# communication.net
KiCad netlist of a schematic drawn in Altium Designer
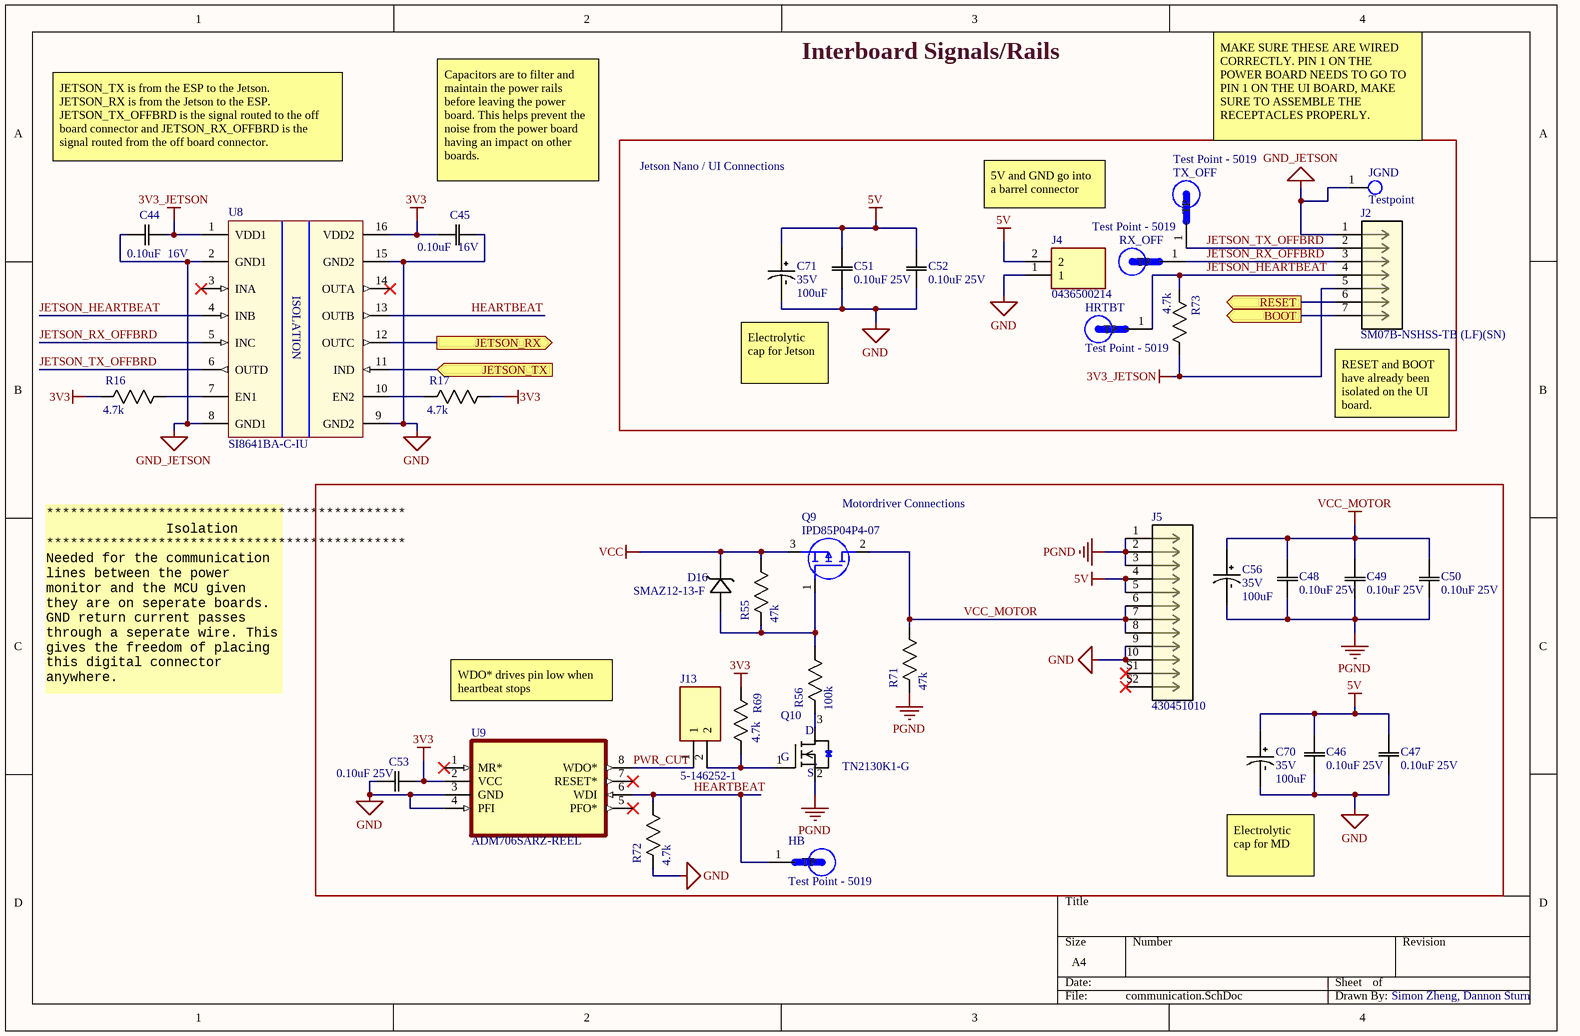
[diagram p0: communication.SchDoc]

(export (version "E")
  (design (tool "Eeschema 10.0.6"))
  (components
    (comp (ref "C44")
      (value "0.10uF")
      (footprint "0603")
      (description "CAP CER 0.10UF 16V X5R 0603")
      (fields
        (field (name "TOLERANCE") "10%")
        (field (name "RATING") "16V")
        (field (name "PART NUMBER") "CAP 0.10uF 16V")
      )
      (libsource (lib "capacitor_library") (part "CAP 0.10uF 16V"))
    )
    (comp (ref "C45")
      (value "0.10uF")
      (footprint "0603")
      (description "CAP CER 0.10UF 16V X5R 0603")
      (fields
        (field (name "TOLERANCE") "10%")
        (field (name "RATING") "16V")
        (field (name "PART NUMBER") "CAP 0.10uF 16V")
      )
      (libsource (lib "capacitor_library") (part "CAP 0.10uF 16V"))
    )
    (comp (ref "C46")
      (value "0.10uF 25V")
      (footprint "0603")
      (description "CAP CER 0.10UF 25V X7R 0603")
      (fields (field (name "TOLERANCE") "10%") (field (name "PART NUMBER") "CAP 0.10uF 25V"))
      (libsource (lib "capacitor_library") (part "CAP 0.10uF 25V"))
    )
    (comp (ref "C47")
      (value "0.10uF 25V")
      (footprint "0603")
      (description "CAP CER 0.10UF 25V X7R 0603")
      (fields (field (name "TOLERANCE") "10%") (field (name "PART NUMBER") "CAP 0.10uF 25V"))
      (libsource (lib "capacitor_library") (part "CAP 0.10uF 25V"))
    )
    (comp (ref "C48")
      (value "0.10uF 25V")
      (footprint "0805")
      (description "CAP CER 0.10UF 25V X7R 0805")
      (fields (field (name "TOLERANCE") "10%") (field (name "PART NUMBER") "CAP 0.10uF 25V"))
      (libsource (lib "capacitor_library") (part "CAP 0.10uF 25V"))
    )
    (comp (ref "C49")
      (value "0.10uF 25V")
      (footprint "0603")
      (description "CAP CER 0.10UF 25V X7R 0603")
      (fields (field (name "TOLERANCE") "10%") (field (name "PART NUMBER") "CAP 0.10uF 25V"))
      (libsource (lib "capacitor_library") (part "CAP 0.10uF 25V"))
    )
    (comp (ref "C50")
      (value "0.10uF 25V")
      (footprint "0603")
      (description "CAP CER 0.10UF 25V X7R 0603")
      (fields (field (name "TOLERANCE") "10%") (field (name "PART NUMBER") "CAP 0.10uF 25V"))
      (libsource (lib "capacitor_library") (part "CAP 0.10uF 25V"))
    )
    (comp (ref "C51")
      (value "0.10uF 25V")
      (footprint "0603")
      (description "CAP CER 0.10UF 25V X7R 0603")
      (fields (field (name "TOLERANCE") "10%") (field (name "PART NUMBER") "CAP 0.10uF 25V"))
      (libsource (lib "capacitor_library") (part "CAP 0.10uF 25V"))
    )
    (comp (ref "C52")
      (value "0.10uF 25V")
      (footprint "0603")
      (description "CAP CER 0.10UF 25V X7R 0603")
      (fields (field (name "TOLERANCE") "10%") (field (name "PART NUMBER") "CAP 0.10uF 25V"))
      (libsource (lib "capacitor_library") (part "CAP 0.10uF 25V"))
    )
    (comp (ref "C53")
      (value "0.10uF 25V")
      (footprint "0603")
      (description "CAP CER 0.10UF 25V X7R 0603")
      (fields (field (name "TOLERANCE") "10%") (field (name "PART NUMBER") "CAP 0.10uF 25V"))
      (libsource (lib "capacitor_library") (part "CAP 0.10uF 25V"))
    )
    (comp (ref "C56")
      (value "100uF")
      (footprint "CAP POL ALU 6.3x5.8")
      (fields
        (field (name "TOLERANCE") "20%")
        (field (name "RATING") "35V")
        (field (name "PART NUMBER") "CAP POL 100uF 35V SMD")
      )
      (libsource (lib "capacitor_library") (part "CAP POL"))
    )
    (comp (ref "C70")
      (value "100uF")
      (footprint "CAP POL ALU 6.3x5.8")
      (fields
        (field (name "TOLERANCE") "20%")
        (field (name "RATING") "35V")
        (field (name "PART NUMBER") "CAP POL 100uF 35V SMD")
      )
      (libsource (lib "capacitor_library") (part "CAP POL"))
    )
    (comp (ref "C71")
      (value "100uF")
      (footprint "CAP POL ALU 6.3x5.8")
      (fields
        (field (name "TOLERANCE") "20%")
        (field (name "RATING") "35V")
        (field (name "PART NUMBER") "CAP POL 100uF 35V SMD")
      )
      (libsource (lib "capacitor_library") (part "CAP POL"))
    )
    (comp (ref "D16")
      (value "SMAZ12-13-F")
      (footprint "SMA_DIO-L")
      (description "Zener Diode 12 V 1 W ±5% Surface Mount SMA")
      (fields
        (field (name "PART NUMBER") "DIODE ZENER 12V 1W")
        (field (name "COPYRIGHT") "Copyright (C) 2021 Ultra Librarian. All rights reserved.")
      )
      (libsource (lib "Diode_Library") (part "DIODE ZENER 12V 1W"))
    )
    (comp (ref "HB")
      (value "Test Point - 5019")
      (footprint "TP380X203")
      (description "PC Test Point, Miniature Phosphor Bronze, Silver Plating Surface Mount Mounting Type")
      (fields (field (name "MP") "5019") (field (name "MF") "Keystone Electronics"))
      (libsource (lib "IC_Library") (part "Test Point - 5019"))
    )
    (comp (ref "HRTBT")
      (value "Test Point - 5019")
      (footprint "TP380X203")
      (description "PC Test Point, Miniature Phosphor Bronze, Silver Plating Surface Mount Mounting Type")
      (fields (field (name "MP") "5019") (field (name "MF") "Keystone Electronics"))
      (libsource (lib "IC_Library") (part "Test Point - 5019"))
    )
    (comp (ref "J2")
      (value "SM07B-NSHSS-TB (LF)(SN)")
      (footprint "JST_SM07B-NSHSS-TB_(LF)(SN)")
      (description "Connector Header Surface Mount, Right Angle 7 position 0.039\" (1.00mm)")
      (fields (field (name "MP") "SM12B-NSHSS-TB (LF)(SN)") (field (name "MF") "JST Sales America Inc."))
      (libsource (lib "Connector_Library") (part "CN 7POS JST NSH SMT RA"))
    )
    (comp (ref "J4")
      (value "0436500214")
      (footprint "43650-0214")
      (description "Connector Header Surface Mount, Right Angle 2 position 0.118\" (3.00mm)")
      (fields
        (field (name "MANUFACTURER_PART_NUMBER") "43650-0214")
        (field (name "PART NUMBER") "CN HDR 2POS Molex 0436500214")
      )
      (libsource (lib "Connector_Library") (part "CN HDR 2POS Molex 0436500214"))
    )
    (comp (ref "J5")
      (value "430451010")
      (footprint "CON_430451010_MOL")
      (description "Connector Header Surface Mount, Right Angle 10 position 0.118\" (3.00mm)")
      (fields
        (field (name "PART NUMBER") "CN HDR 10POS MOLEX 430451010")
        (field (name "COPYRIGHT") "Copyright (C) 2021 Ultra Librarian. All rights reserved.")
      )
      (libsource (lib "Connector_Library") (part "CN HDR 10POS MOLEX 430451010"))
    )
    (comp (ref "J13")
      (value "5-146252-1")
      (footprint "TE_5-146252-1")
      (description "2 Pin Jumper Male Pins and Cap")
      (libsource (lib "Connector_Library") (part "5-146252-1"))
    )
    (comp (ref "JGND")
      (value "Testpoint")
      (footprint "TP_1mm")
      (fields (field (name "PART NUMBER") "TP_1MM"))
      (libsource (lib "IC_Library") (part "Testpoint"))
    )
    (comp (ref "Q9")
      (value "IPD85P04P4-07")
      (footprint "DPAK (TO-252)")
      (description "P-Channel 40 V 85A (Tc) 88W (Tc) Surface Mount PG-TO252-3-313")
      (fields (field (name "PART NUMBER") "MOSFET IPD85P04P4-07"))
      (libsource (lib "Transistor_Library") (part "MOSFET IPD85P04P4-07"))
    )
    (comp (ref "Q10")
      (value "TN2130K1-G")
      (footprint "SOT95P237X112-3N")
      (description "N-Channel 300 V 85mA (Tj) 360mW (Tc) Surface Mount TO-236AB (SOT23)")
      (fields
        (field (name "PART NUMBER") "MOSFET N-CH TN2130K1-G")
        (field (name "COPYRIGHT") "Copyright (C) 2021 Ultra Librarian. All rights reserved.")
      )
      (libsource (lib "Transistor_Library") (part "MOSFET N-CH TN2130K1-G"))
    )
    (comp (ref "R16")
      (value "4.7k")
      (footprint "0603")
      (description "RES SMD 4.7k OHM 5% 1/8W 0603")
      (fields (field (name "TOLERANCE") "5%") (field (name "PART NUMBER") "RES 4.7k 1/8W - 5%"))
      (libsource (lib "") (part "RES 4.7k 1/8W - 5%_1"))
    )
    (comp (ref "R17")
      (value "4.7k")
      (footprint "0603")
      (description "RES SMD 4.7k OHM 5% 1/8W 0603")
      (fields (field (name "TOLERANCE") "5%") (field (name "PART NUMBER") "RES 4.7k 1/8W - 5%"))
      (libsource (lib "Resistor_Library") (part "RES 4.7k 1/8W - 5%"))
    )
    (comp (ref "R55")
      (value "47k")
      (footprint "0603")
      (description "RES SMD 47k OHM 5% 1/8W 0603")
      (fields (field (name "TOLERANCE") "5%") (field (name "PART NUMBER") "RES 47k 1/8W - 5%"))
      (libsource (lib "Resistor_Library") (part "RES 47k 1/8W - 5%"))
    )
    (comp (ref "R56")
      (value "100k")
      (footprint "0603")
      (description "RES SMD 100K OHM 5% 1/8W 0603")
      (fields (field (name "TOLERANCE") "5%") (field (name "PART NUMBER") "RES 100k 1/8W - 5%"))
      (libsource (lib "Resistor_Library") (part "RES 100k 1/8W 5%"))
    )
    (comp (ref "R69")
      (value "4.7k")
      (footprint "0603")
      (description "RES SMD 4.7k OHM 5% 1/8W 0603")
      (fields (field (name "TOLERANCE") "5%") (field (name "PART NUMBER") "RES 4.7k 1/8W - 5%"))
      (libsource (lib "Resistor_Library") (part "RES 4.7k 1/8W - 5%"))
    )
    (comp (ref "R71")
      (value "47k")
      (footprint "0603")
      (description "RES SMD 47k OHM 5% 1/8W 0603")
      (fields (field (name "TOLERANCE") "5%") (field (name "PART NUMBER") "RES 47k 1/8W - 5%"))
      (libsource (lib "Resistor_Library") (part "RES 47k 1/8W - 5%"))
    )
    (comp (ref "R72")
      (value "4.7k")
      (footprint "0603")
      (description "RES SMD 4.7k OHM 5% 1/8W 0603")
      (fields (field (name "TOLERANCE") "5%") (field (name "PART NUMBER") "RES 4.7k 1/8W - 5%"))
      (libsource (lib "Resistor_Library") (part "RES 4.7k 1/8W - 5%"))
    )
    (comp (ref "R73")
      (value "4.7k")
      (footprint "0603")
      (description "RES SMD 4.7k OHM 5% 1/8W 0603")
      (fields (field (name "TOLERANCE") "5%") (field (name "PART NUMBER") "RES 4.7k 1/8W - 5%"))
      (libsource (lib "") (part "RES 4.7k 1/8W - 5%_1"))
    )
    (comp (ref "RX_OFF")
      (value "Test Point - 5019")
      (footprint "TP380X203")
      (description "PC Test Point, Miniature Phosphor Bronze, Silver Plating Surface Mount Mounting Type")
      (fields (field (name "MP") "5019") (field (name "MF") "Keystone Electronics"))
      (libsource (lib "IC_Library") (part "Test Point - 5019"))
    )
    (comp (ref "TX_OFF")
      (value "Test Point - 5019")
      (footprint "TP380X203")
      (description "PC Test Point, Miniature Phosphor Bronze, Silver Plating Surface Mount Mounting Type")
      (fields (field (name "MP") "5019") (field (name "MF") "Keystone Electronics"))
      (libsource (lib "IC_Library") (part "Test Point - 5019"))
    )
    (comp (ref "U8")
      (value "SI8641BA-C-IU")
      (footprint "SOP64P600X175-16N")
      (fields (field (name "PART NUMBER") "ISO SI8641BA-C-IU"))
      (libsource (lib "IC_Library") (part "ISO SI8641BA-C-IU"))
    )
    (comp (ref "U9")
      (value "ADM706SARZ-REEL")
      (footprint "SOIC127P600X175-8N")
      (fields
        (field (name "DIGI-KEY_PART_NUMBER") "ADM706SARZ-REELCT-ND")
        (field (name "MF") "Analog Devices")
      )
      (libsource (lib "IC_Library") (part "ADM706SARZ-REEL"))
    )
  )
  (nets
    (net (code "1") (name "/BOOT") (class "Default")
      (node (ref "J2") (pin "7") (pinfunction "7_7") (pintype "passive"))
    )
    (net (code "2") (name "/HEARTBEAT") (class "Default")
      (node (ref "HB") (pin "1") (pinfunction "TP_1") (pintype "passive"))
      (node (ref "R72") (pin "1") (pinfunction "R1_1") (pintype "passive"))
      (node (ref "U8") (pin "13") (pinfunction "OUTB_13") (pintype "output"))
      (node (ref "U9") (pin "6") (pinfunction "WDI_6") (pintype "input"))
    )
    (net (code "3") (name "/JETSON_HEARTBEAT") (class "Default")
      (node (ref "HRTBT") (pin "1") (pinfunction "TP_1") (pintype "passive"))
      (node (ref "J2") (pin "4") (pinfunction "4_4") (pintype "passive"))
      (node (ref "R73") (pin "2") (pinfunction "R2_2") (pintype "passive"))
      (node (ref "U8") (pin "4") (pinfunction "INB_4") (pintype "input"))
    )
    (net (code "4") (name "/JETSON_RX") (class "Default")
      (node (ref "U8") (pin "12") (pinfunction "OUTC_12") (pintype "output"))
    )
    (net (code "5") (name "/JETSON_RX_OFFBRD") (class "Default")
      (node (ref "J2") (pin "3") (pinfunction "3_3") (pintype "passive"))
      (node (ref "RX_OFF") (pin "1") (pinfunction "TP_1") (pintype "passive"))
      (node (ref "U8") (pin "5") (pinfunction "INC_5") (pintype "input"))
    )
    (net (code "6") (name "/JETSON_TX") (class "Default")
      (node (ref "U8") (pin "11") (pinfunction "IND_11") (pintype "input"))
    )
    (net (code "7") (name "/JETSON_TX_OFFBRD") (class "Default")
      (node (ref "J2") (pin "2") (pinfunction "2_2") (pintype "passive"))
      (node (ref "TX_OFF") (pin "1") (pinfunction "TP_1") (pintype "passive"))
      (node (ref "U8") (pin "6") (pinfunction "OUTD_6") (pintype "output"))
    )
    (net (code "8") (name "/PWR_CUT") (class "Default")
      (node (ref "J13") (pin "1") (pinfunction "1_1") (pintype "passive"))
      (node (ref "U9") (pin "8") (pinfunction "WDO*_8") (pintype "output"))
    )
    (net (code "9") (name "/RESET") (class "Default")
      (node (ref "J2") (pin "6") (pinfunction "6_6") (pintype "passive"))
    )
    (net (code "10") (name "3V3") (class "Default")
      (node (ref "C45") (pin "2") (pinfunction "C2_2") (pintype "passive"))
      (node (ref "C53") (pin "2") (pinfunction "C2_2") (pintype "passive"))
      (node (ref "R16") (pin "2") (pinfunction "R2_2") (pintype "passive"))
      (node (ref "R17") (pin "1") (pinfunction "R1_1") (pintype "passive"))
      (node (ref "R69") (pin "2") (pinfunction "R2_2") (pintype "passive"))
      (node (ref "U8") (pin "16") (pinfunction "VDD2_16") (pintype "power_in"))
      (node (ref "U9") (pin "2") (pinfunction "VCC_2") (pintype "power_in"))
    )
    (net (code "11") (name "3V3_JETSON") (class "Default")
      (node (ref "C44") (pin "2") (pinfunction "C2_2") (pintype "passive"))
      (node (ref "J2") (pin "5") (pinfunction "5_5") (pintype "passive"))
      (node (ref "R73") (pin "1") (pinfunction "R1_1") (pintype "passive"))
      (node (ref "U8") (pin "1") (pinfunction "VDD1_1") (pintype "power_in"))
    )
    (net (code "12") (name "5V") (class "Default")
      (node (ref "C46") (pin "2") (pinfunction "C2_2") (pintype "passive"))
      (node (ref "C47") (pin "2") (pinfunction "C2_2") (pintype "passive"))
      (node (ref "C51") (pin "2") (pinfunction "C2_2") (pintype "passive"))
      (node (ref "C52") (pin "2") (pinfunction "C2_2") (pintype "passive"))
      (node (ref "C70") (pin "POS") (pinfunction "POS_POS") (pintype "passive"))
      (node (ref "C71") (pin "POS") (pinfunction "POS_POS") (pintype "passive"))
      (node (ref "J4") (pin "2") (pinfunction "2_2") (pintype "passive"))
      (node (ref "J5") (pin "4") (pinfunction "4_4") (pintype "passive"))
      (node (ref "J5") (pin "5") (pinfunction "5_5") (pintype "passive"))
    )
    (net (code "13") (name "GND") (class "Default")
      (node (ref "C45") (pin "1") (pinfunction "C1_1") (pintype "passive"))
      (node (ref "C46") (pin "1") (pinfunction "C1_1") (pintype "passive"))
      (node (ref "C47") (pin "1") (pinfunction "C1_1") (pintype "passive"))
      (node (ref "C51") (pin "1") (pinfunction "C1_1") (pintype "passive"))
      (node (ref "C52") (pin "1") (pinfunction "C1_1") (pintype "passive"))
      (node (ref "C53") (pin "1") (pinfunction "C1_1") (pintype "passive"))
      (node (ref "C70") (pin "NEG") (pinfunction "NEG_NEG") (pintype "passive"))
      (node (ref "C71") (pin "NEG") (pinfunction "NEG_NEG") (pintype "passive"))
      (node (ref "J4") (pin "1") (pinfunction "1_1") (pintype "passive"))
      (node (ref "J5") (pin "10") (pinfunction "10_10") (pintype "passive"))
      (node (ref "J5") (pin "9") (pinfunction "9_9") (pintype "passive"))
      (node (ref "R72") (pin "2") (pinfunction "R2_2") (pintype "passive"))
      (node (ref "U8") (pin "15") (pinfunction "GND2_15") (pintype "power_in"))
      (node (ref "U8") (pin "9") (pinfunction "GND2_9") (pintype "power_in"))
      (node (ref "U9") (pin "3") (pinfunction "GND_3") (pintype "passive"))
      (node (ref "U9") (pin "4") (pinfunction "PFI_4") (pintype "input"))
    )
    (net (code "14") (name "GND_JETSON") (class "Default")
      (node (ref "C44") (pin "1") (pinfunction "C1_1") (pintype "passive"))
      (node (ref "J2") (pin "1") (pinfunction "1_1") (pintype "passive"))
      (node (ref "JGND") (pin "1") (pinfunction "TP_1") (pintype "passive"))
      (node (ref "U8") (pin "2") (pinfunction "GND1_2") (pintype "power_in"))
      (node (ref "U8") (pin "8") (pinfunction "GND1_8") (pintype "power_in"))
    )
    (net (code "15") (name "Net-(Q9-G)") (class "Default")
      (node (ref "D16") (pin "2") (pinfunction "2_2") (pintype "passive"))
      (node (ref "Q9") (pin "1") (pinfunction "G_1") (pintype "passive"))
      (node (ref "R55") (pin "2") (pinfunction "R2_2") (pintype "passive"))
      (node (ref "R56") (pin "1") (pinfunction "R1_1") (pintype "passive"))
    )
    (net (code "16") (name "Net-(Q10-D)") (class "Default")
      (node (ref "Q10") (pin "3") (pinfunction "D_3") (pintype "passive"))
      (node (ref "R56") (pin "2") (pinfunction "R2_2") (pintype "passive"))
    )
    (net (code "17") (name "Net-(Q10-G)") (class "Default")
      (node (ref "J13") (pin "2") (pinfunction "2_2") (pintype "passive"))
      (node (ref "Q10") (pin "1") (pinfunction "G_1") (pintype "passive"))
      (node (ref "R69") (pin "1") (pinfunction "R1_1") (pintype "passive"))
    )
    (net (code "18") (name "Net-(R16-R1)") (class "Default")
      (node (ref "R16") (pin "1") (pinfunction "R1_1") (pintype "passive"))
      (node (ref "U8") (pin "7") (pinfunction "EN1_7") (pintype "passive"))
    )
    (net (code "19") (name "Net-(R17-R2)") (class "Default")
      (node (ref "R17") (pin "2") (pinfunction "R2_2") (pintype "passive"))
      (node (ref "U8") (pin "10") (pinfunction "EN2_10") (pintype "passive"))
    )
    (net (code "20") (name "PGND") (class "Default")
      (node (ref "C48") (pin "1") (pinfunction "C1_1") (pintype "passive"))
      (node (ref "C49") (pin "1") (pinfunction "C1_1") (pintype "passive"))
      (node (ref "C50") (pin "1") (pinfunction "C1_1") (pintype "passive"))
      (node (ref "C56") (pin "NEG") (pinfunction "NEG_NEG") (pintype "passive"))
      (node (ref "J5") (pin "1") (pinfunction "1_1") (pintype "passive"))
      (node (ref "J5") (pin "2") (pinfunction "2_2") (pintype "passive"))
      (node (ref "J5") (pin "3") (pinfunction "3_3") (pintype "passive"))
      (node (ref "Q10") (pin "2") (pinfunction "S_2") (pintype "passive"))
      (node (ref "R71") (pin "2") (pinfunction "R2_2") (pintype "passive"))
    )
    (net (code "21") (name "VCC") (class "Default")
      (node (ref "D16") (pin "1") (pinfunction "1_1") (pintype "passive"))
      (node (ref "Q9") (pin "3") (pinfunction "S_3") (pintype "passive"))
      (node (ref "R55") (pin "1") (pinfunction "R1_1") (pintype "passive"))
    )
    (net (code "22") (name "VCC_MOTOR") (class "Default")
      (node (ref "C48") (pin "2") (pinfunction "C2_2") (pintype "passive"))
      (node (ref "C49") (pin "2") (pinfunction "C2_2") (pintype "passive"))
      (node (ref "C50") (pin "2") (pinfunction "C2_2") (pintype "passive"))
      (node (ref "C56") (pin "POS") (pinfunction "POS_POS") (pintype "passive"))
      (node (ref "J5") (pin "6") (pinfunction "6_6") (pintype "passive"))
      (node (ref "J5") (pin "7") (pinfunction "7_7") (pintype "passive"))
      (node (ref "J5") (pin "8") (pinfunction "8_8") (pintype "passive"))
      (node (ref "Q9") (pin "2") (pinfunction "D_2") (pintype "passive"))
      (node (ref "R71") (pin "1") (pinfunction "R1_1") (pintype "passive"))
    )
    (net (code "23") (name "unconnected-(J5-PadS1)") (class "Default")
      (node (ref "J5") (pin "S1") (pinfunction "S1_S1") (pintype "passive+no_connect"))
    )
    (net (code "24") (name "unconnected-(J5-PadS2)") (class "Default")
      (node (ref "J5") (pin "S2") (pinfunction "S2_S2") (pintype "passive+no_connect"))
    )
    (net (code "25") (name "unconnected-(U8-INA-Pad3)") (class "Default")
      (node (ref "U8") (pin "3") (pinfunction "INA_3") (pintype "input+no_connect"))
    )
    (net (code "26") (name "unconnected-(U8-OUTA-Pad14)") (class "Default")
      (node (ref "U8") (pin "14") (pinfunction "OUTA_14") (pintype "output+no_connect"))
    )
    (net (code "27") (name "unconnected-(U9-MR*-Pad1)") (class "Default")
      (node (ref "U9") (pin "1") (pinfunction "MR*_1") (pintype "input+no_connect"))
    )
    (net (code "28") (name "unconnected-(U9-PFO*-Pad5)") (class "Default")
      (node (ref "U9") (pin "5") (pinfunction "PFO*_5") (pintype "output+no_connect"))
    )
    (net (code "29") (name "unconnected-(U9-RESET*-Pad7)") (class "Default")
      (node (ref "U9") (pin "7") (pinfunction "RESET*_7") (pintype "output+no_connect"))
    )
  )
)
